# oLoRa-part-motherboard.net
KiCad netlist of a schematic drawn in EasyEDA
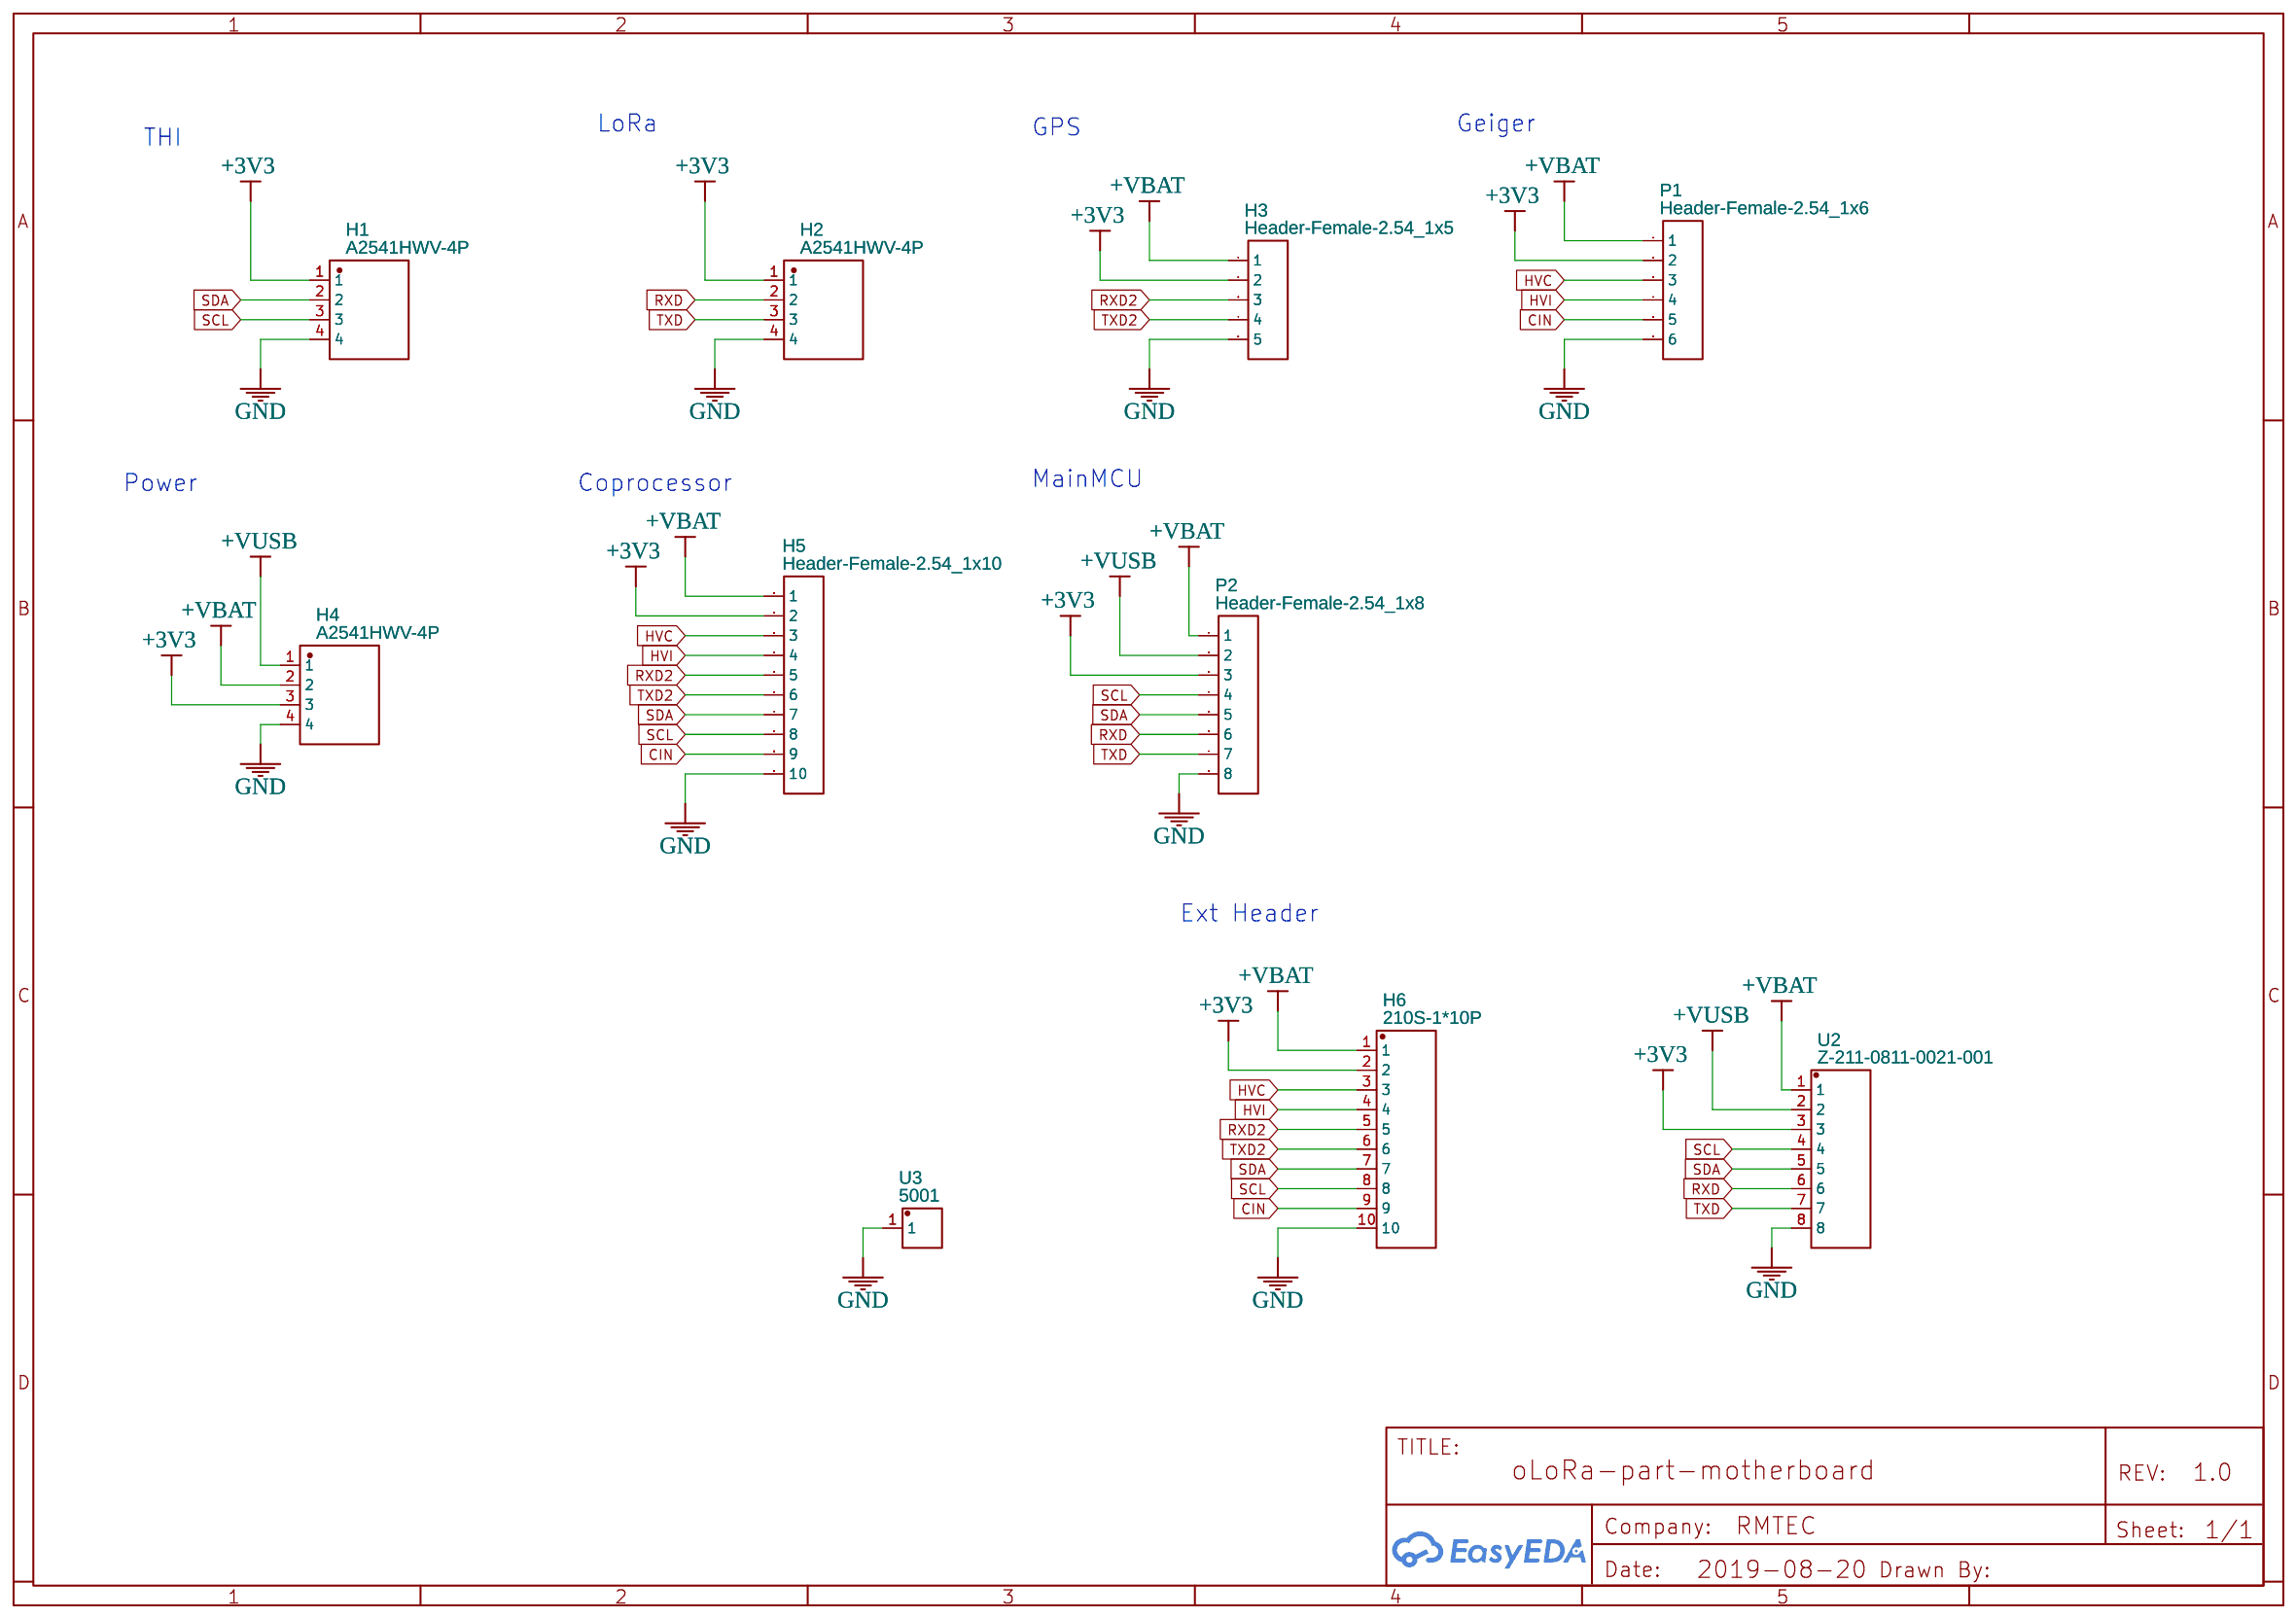
[diagram p0: schematic sheet]

(export (version "E")
  (design (tool "Eeschema 10.0.6"))
  (components
    (comp (ref "H1")
      (value "A2541HWV-4P")
      (fields (field (name "BOM_Supplier Part") "C225501"))
      (libsource (lib "") (part "Unknown_175_150"))
    )
    (comp (ref "H2")
      (value "A2541HWV-4P")
      (fields (field (name "BOM_Supplier Part") "C225501"))
      (libsource (lib "") (part "Unknown_405_150"))
    )
    (comp (ref "H3")
      (value "Header-Female-2.54_1x5")
      (fields
        (field (name "BOM_Manufacturer Part") "2.54mm 1*5p Female header")
        (field (name "BOM_Supplier Part") "C50950")
      )
      (libsource (lib "") (part "Unknown_630_145"))
    )
    (comp (ref "H4")
      (value "A2541HWV-4P")
      (fields (field (name "BOM_Supplier Part") "C225501"))
      (libsource (lib "") (part "Unknown_160_345"))
    )
    (comp (ref "H5")
      (value "Header-Female-2.54_1x10")
      (fields
        (field (name "BOM_Manufacturer Part") "2.54mm 1*10P Straight Female header Gold-plated")
        (field (name "BOM_Supplier Part") "C35445")
      )
      (libsource (lib "") (part "Unknown_390_345"))
    )
    (comp (ref "H6")
      (value "210S-1*10P")
      (fields
        (field (name "BOM_Manufacturer Part") "210S-1*10P L=11.6MMGold-plated black")
        (field (name "BOM_Supplier Part") "C124372")
      )
      (libsource (lib "") (part "Unknown_700_570"))
    )
    (comp (ref "P1")
      (value "Header-Female-2.54_1x6")
      (fields
        (field (name "BOM_Manufacturer Part") "Female header 1*6p")
        (field (name "BOM_Supplier Part") "C40877")
      )
      (libsource (lib "") (part "Unknown_840_140"))
    )
    (comp (ref "P2")
      (value "Header-Female-2.54_1x8")
      (fields
        (field (name "BOM_Manufacturer Part") "Female headerHDR1X8-2.54")
        (field (name "BOM_Supplier Part") "C27438")
      )
      (libsource (lib "") (part "Unknown_615_350"))
    )
    (comp (ref "U2")
      (value "Z-211-0811-0021-001")
      (fields (field (name "BOM_Supplier Part") "C190820"))
      (libsource (lib "") (part "Unknown_920_580"))
    )
    (comp (ref "U3")
      (value "5001")
      (fields (field (name "BOM_Supplier Part") "C238122"))
      (libsource (lib "") (part "Unknown_460_615"))
    )
  )
  (nets
    (net (code "1") (name "+3V3") (class "Default")
      (node (ref "H1") (pin "1") (pinfunction "1_1") (pintype "unspecified"))
      (node (ref "H2") (pin "1") (pinfunction "1_1") (pintype "unspecified"))
      (node (ref "H3") (pin "2") (pinfunction "2_2") (pintype "input"))
      (node (ref "H4") (pin "3") (pinfunction "3_3") (pintype "unspecified"))
      (node (ref "H5") (pin "2") (pinfunction "2_2") (pintype "input"))
      (node (ref "H6") (pin "2") (pinfunction "2_2") (pintype "unspecified"))
      (node (ref "P1") (pin "2") (pinfunction "2_2") (pintype "input"))
      (node (ref "P2") (pin "3") (pinfunction "3_3") (pintype "input"))
      (node (ref "U2") (pin "3") (pinfunction "3_3") (pintype "unspecified"))
    )
    (net (code "2") (name "+VBAT") (class "Default")
      (node (ref "H3") (pin "1") (pinfunction "1_1") (pintype "input"))
      (node (ref "H4") (pin "2") (pinfunction "2_2") (pintype "unspecified"))
      (node (ref "H5") (pin "1") (pinfunction "1_1") (pintype "input"))
      (node (ref "H6") (pin "1") (pinfunction "1_1") (pintype "unspecified"))
      (node (ref "P1") (pin "1") (pinfunction "1_1") (pintype "input"))
      (node (ref "P2") (pin "1") (pinfunction "1_1") (pintype "input"))
      (node (ref "U2") (pin "1") (pinfunction "1_1") (pintype "unspecified"))
    )
    (net (code "3") (name "+VUSB") (class "Default")
      (node (ref "H4") (pin "1") (pinfunction "1_1") (pintype "unspecified"))
      (node (ref "P2") (pin "2") (pinfunction "2_2") (pintype "input"))
      (node (ref "U2") (pin "2") (pinfunction "2_2") (pintype "unspecified"))
    )
    (net (code "4") (name "CIN") (class "Default")
      (node (ref "H5") (pin "9") (pinfunction "9_9") (pintype "input"))
      (node (ref "H6") (pin "9") (pinfunction "9_9") (pintype "unspecified"))
      (node (ref "P1") (pin "5") (pinfunction "5_5") (pintype "input"))
    )
    (net (code "5") (name "GND") (class "Default")
      (node (ref "H1") (pin "4") (pinfunction "4_4") (pintype "unspecified"))
      (node (ref "H2") (pin "4") (pinfunction "4_4") (pintype "unspecified"))
      (node (ref "H3") (pin "5") (pinfunction "5_5") (pintype "input"))
      (node (ref "H4") (pin "4") (pinfunction "4_4") (pintype "unspecified"))
      (node (ref "H5") (pin "10") (pinfunction "10_10") (pintype "input"))
      (node (ref "H6") (pin "10") (pinfunction "10_10") (pintype "unspecified"))
      (node (ref "P1") (pin "6") (pinfunction "6_6") (pintype "input"))
      (node (ref "P2") (pin "8") (pinfunction "8_8") (pintype "input"))
      (node (ref "U2") (pin "8") (pinfunction "8_8") (pintype "unspecified"))
      (node (ref "U3") (pin "1") (pinfunction "1_1") (pintype "unspecified"))
    )
    (net (code "6") (name "HVC") (class "Default")
      (node (ref "H5") (pin "3") (pinfunction "3_3") (pintype "input"))
      (node (ref "H6") (pin "3") (pinfunction "3_3") (pintype "unspecified"))
      (node (ref "P1") (pin "3") (pinfunction "3_3") (pintype "input"))
    )
    (net (code "7") (name "HVI") (class "Default")
      (node (ref "H5") (pin "4") (pinfunction "4_4") (pintype "input"))
      (node (ref "H6") (pin "4") (pinfunction "4_4") (pintype "unspecified"))
      (node (ref "P1") (pin "4") (pinfunction "4_4") (pintype "input"))
    )
    (net (code "8") (name "RXD") (class "Default")
      (node (ref "H2") (pin "2") (pinfunction "2_2") (pintype "unspecified"))
      (node (ref "P2") (pin "6") (pinfunction "6_6") (pintype "input"))
      (node (ref "U2") (pin "6") (pinfunction "6_6") (pintype "unspecified"))
    )
    (net (code "9") (name "RXD2") (class "Default")
      (node (ref "H3") (pin "3") (pinfunction "3_3") (pintype "input"))
      (node (ref "H5") (pin "5") (pinfunction "5_5") (pintype "input"))
      (node (ref "H6") (pin "5") (pinfunction "5_5") (pintype "unspecified"))
    )
    (net (code "10") (name "SCL") (class "Default")
      (node (ref "H1") (pin "3") (pinfunction "3_3") (pintype "unspecified"))
      (node (ref "H5") (pin "8") (pinfunction "8_8") (pintype "input"))
      (node (ref "H6") (pin "8") (pinfunction "8_8") (pintype "unspecified"))
      (node (ref "P2") (pin "4") (pinfunction "4_4") (pintype "input"))
      (node (ref "U2") (pin "4") (pinfunction "4_4") (pintype "unspecified"))
    )
    (net (code "11") (name "SDA") (class "Default")
      (node (ref "H1") (pin "2") (pinfunction "2_2") (pintype "unspecified"))
      (node (ref "H5") (pin "7") (pinfunction "7_7") (pintype "input"))
      (node (ref "H6") (pin "7") (pinfunction "7_7") (pintype "unspecified"))
      (node (ref "P2") (pin "5") (pinfunction "5_5") (pintype "input"))
      (node (ref "U2") (pin "5") (pinfunction "5_5") (pintype "unspecified"))
    )
    (net (code "12") (name "TXD") (class "Default")
      (node (ref "H2") (pin "3") (pinfunction "3_3") (pintype "unspecified"))
      (node (ref "P2") (pin "7") (pinfunction "7_7") (pintype "input"))
      (node (ref "U2") (pin "7") (pinfunction "7_7") (pintype "unspecified"))
    )
    (net (code "13") (name "TXD2") (class "Default")
      (node (ref "H3") (pin "4") (pinfunction "4_4") (pintype "input"))
      (node (ref "H5") (pin "6") (pinfunction "6_6") (pintype "input"))
      (node (ref "H6") (pin "6") (pinfunction "6_6") (pintype "unspecified"))
    )
  )
)
